# LCD.net
KiCad netlist of a schematic drawn in Altium Designer
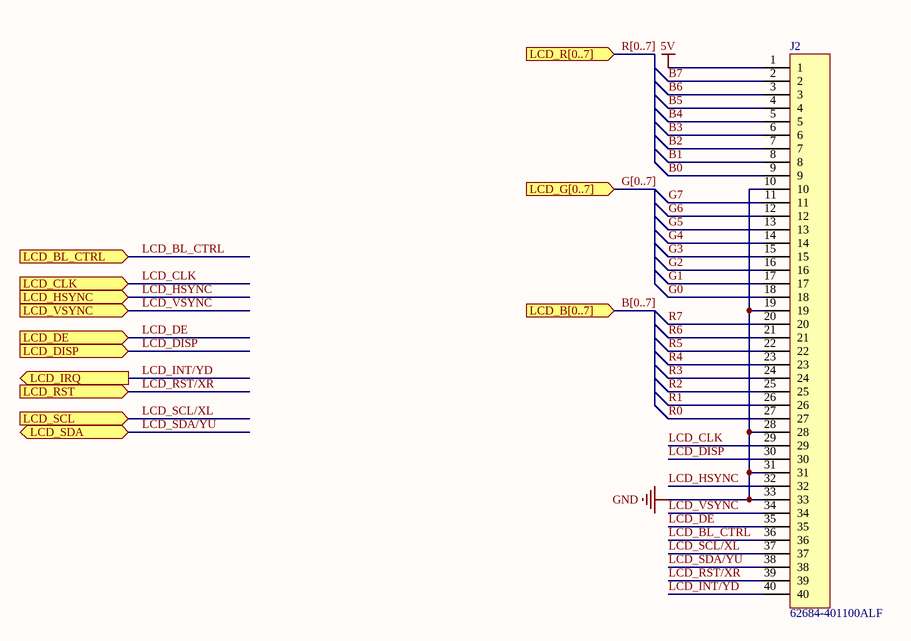
[diagram p0: LCD.SchDoc]

(export (version "E")
  (design (tool "Eeschema 10.0.6"))
  (components
    (comp (ref "J2")
      (value "62684-401100ALF")
      (footprint "fpc-40")
      (description "Connector")
      (fields (field (name "MANUFACTURER") "Amphenol FCI"))
      (libsource (lib "yildizIoT Library") (part "FPC-40"))
    )
  )
  (nets
    (net (code "1") (name "/B0") (class "Default")
      (node (ref "J2") (pin "9") (pinfunction "9_9") (pintype "passive"))
    )
    (net (code "2") (name "/B1") (class "Default")
      (node (ref "J2") (pin "8") (pinfunction "8_8") (pintype "passive"))
    )
    (net (code "3") (name "/B2") (class "Default")
      (node (ref "J2") (pin "7") (pinfunction "7_7") (pintype "passive"))
    )
    (net (code "4") (name "/B3") (class "Default")
      (node (ref "J2") (pin "6") (pinfunction "6_6") (pintype "passive"))
    )
    (net (code "5") (name "/B4") (class "Default")
      (node (ref "J2") (pin "5") (pinfunction "5_5") (pintype "passive"))
    )
    (net (code "6") (name "/B5") (class "Default")
      (node (ref "J2") (pin "4") (pinfunction "4_4") (pintype "passive"))
    )
    (net (code "7") (name "/B6") (class "Default")
      (node (ref "J2") (pin "3") (pinfunction "3_3") (pintype "passive"))
    )
    (net (code "8") (name "/B7") (class "Default")
      (node (ref "J2") (pin "2") (pinfunction "2_2") (pintype "passive"))
    )
    (net (code "10") (name "/G0") (class "Default")
      (node (ref "J2") (pin "18") (pinfunction "18_18") (pintype "passive"))
    )
    (net (code "11") (name "/G1") (class "Default")
      (node (ref "J2") (pin "17") (pinfunction "17_17") (pintype "passive"))
    )
    (net (code "12") (name "/G2") (class "Default")
      (node (ref "J2") (pin "16") (pinfunction "16_16") (pintype "passive"))
    )
    (net (code "13") (name "/G3") (class "Default")
      (node (ref "J2") (pin "15") (pinfunction "15_15") (pintype "passive"))
    )
    (net (code "14") (name "/G4") (class "Default")
      (node (ref "J2") (pin "14") (pinfunction "14_14") (pintype "passive"))
    )
    (net (code "15") (name "/G5") (class "Default")
      (node (ref "J2") (pin "13") (pinfunction "13_13") (pintype "passive"))
    )
    (net (code "16") (name "/G6") (class "Default")
      (node (ref "J2") (pin "12") (pinfunction "12_12") (pintype "passive"))
    )
    (net (code "17") (name "/G7") (class "Default")
      (node (ref "J2") (pin "11") (pinfunction "11_11") (pintype "passive"))
    )
    (net (code "19") (name "/LCD_BL_CTRL") (class "Default")
      (node (ref "J2") (pin "36") (pinfunction "36_36") (pintype "passive"))
    )
    (net (code "20") (name "/LCD_CLK") (class "Default")
      (node (ref "J2") (pin "29") (pinfunction "29_29") (pintype "passive"))
    )
    (net (code "21") (name "/LCD_DE") (class "Default")
      (node (ref "J2") (pin "35") (pinfunction "35_35") (pintype "passive"))
    )
    (net (code "22") (name "/LCD_DISP") (class "Default")
      (node (ref "J2") (pin "30") (pinfunction "30_30") (pintype "passive"))
    )
    (net (code "23") (name "/LCD_HSYNC") (class "Default")
      (node (ref "J2") (pin "32") (pinfunction "32_32") (pintype "passive"))
    )
    (net (code "24") (name "/LCD_INT{slash}YD") (class "Default")
      (node (ref "J2") (pin "40") (pinfunction "40_40") (pintype "passive"))
    )
    (net (code "25") (name "/LCD_RST{slash}XR") (class "Default")
      (node (ref "J2") (pin "39") (pinfunction "39_39") (pintype "passive"))
    )
    (net (code "26") (name "/LCD_SCL{slash}XL") (class "Default")
      (node (ref "J2") (pin "37") (pinfunction "37_37") (pintype "passive"))
    )
    (net (code "27") (name "/LCD_SDA{slash}YU") (class "Default")
      (node (ref "J2") (pin "38") (pinfunction "38_38") (pintype "passive"))
    )
    (net (code "28") (name "/LCD_VSYNC") (class "Default")
      (node (ref "J2") (pin "34") (pinfunction "34_34") (pintype "passive"))
    )
    (net (code "29") (name "/R0") (class "Default")
      (node (ref "J2") (pin "27") (pinfunction "27_27") (pintype "passive"))
    )
    (net (code "30") (name "/R1") (class "Default")
      (node (ref "J2") (pin "26") (pinfunction "26_26") (pintype "passive"))
    )
    (net (code "31") (name "/R2") (class "Default")
      (node (ref "J2") (pin "25") (pinfunction "25_25") (pintype "passive"))
    )
    (net (code "32") (name "/R3") (class "Default")
      (node (ref "J2") (pin "24") (pinfunction "24_24") (pintype "passive"))
    )
    (net (code "33") (name "/R4") (class "Default")
      (node (ref "J2") (pin "23") (pinfunction "23_23") (pintype "passive"))
    )
    (net (code "34") (name "/R5") (class "Default")
      (node (ref "J2") (pin "22") (pinfunction "22_22") (pintype "passive"))
    )
    (net (code "35") (name "/R6") (class "Default")
      (node (ref "J2") (pin "21") (pinfunction "21_21") (pintype "passive"))
    )
    (net (code "36") (name "/R7") (class "Default")
      (node (ref "J2") (pin "20") (pinfunction "20_20") (pintype "passive"))
    )
    (net (code "38") (name "5V") (class "Default")
      (node (ref "J2") (pin "1") (pinfunction "1_1") (pintype "passive"))
    )
    (net (code "39") (name "GND") (class "Default")
      (node (ref "J2") (pin "10") (pinfunction "10_10") (pintype "passive"))
      (node (ref "J2") (pin "19") (pinfunction "19_19") (pintype "passive"))
      (node (ref "J2") (pin "28") (pinfunction "28_28") (pintype "passive"))
      (node (ref "J2") (pin "31") (pinfunction "31_31") (pintype "passive"))
      (node (ref "J2") (pin "33") (pinfunction "33_33") (pintype "passive"))
    )
  )
)
